# MotorDriver.net
KiCad netlist of a schematic drawn in EAGLE
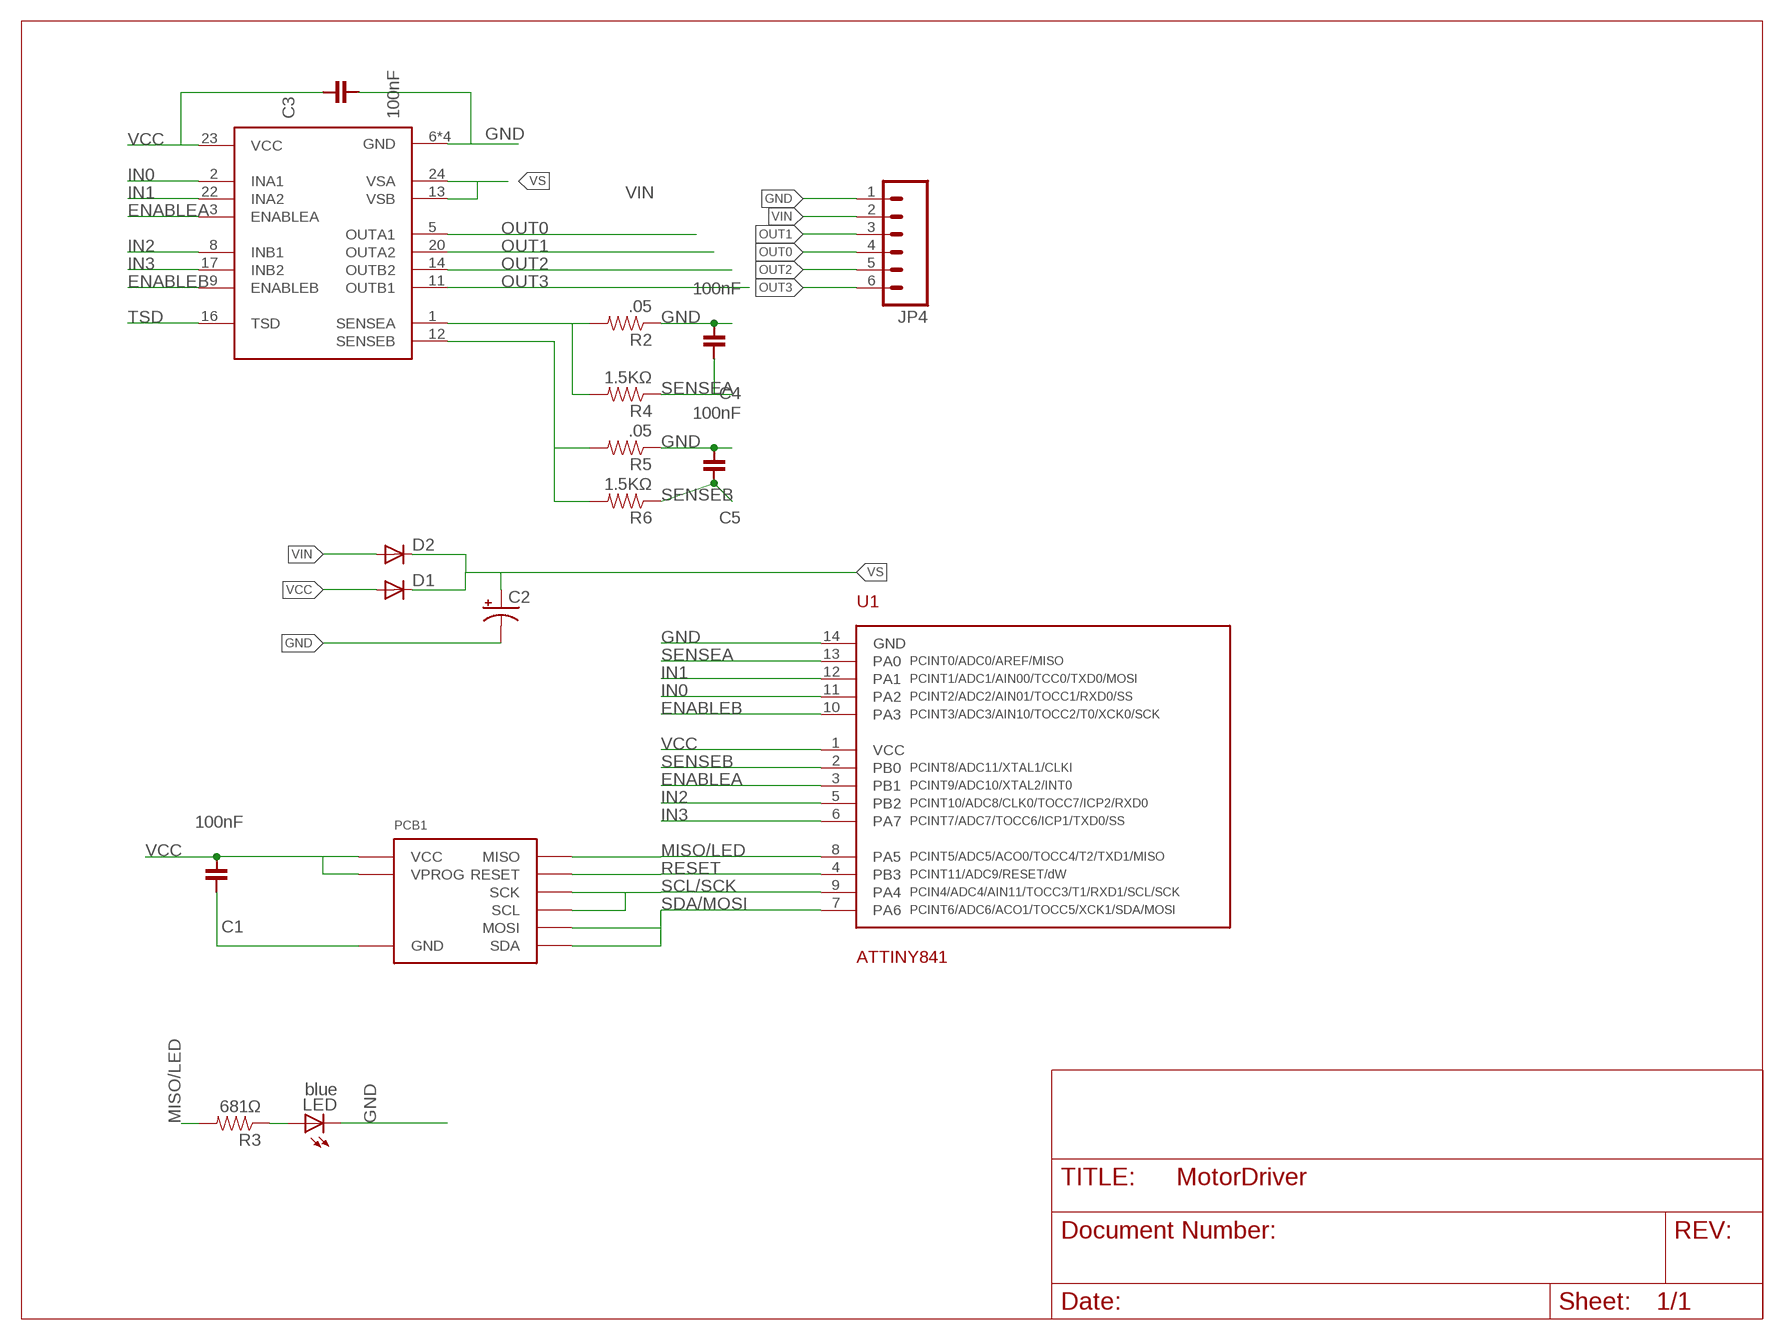
[diagram p0: schematic, sheet 1]

(export (version "E")
  (design (tool "Eeschema 10.0.6"))
  (components
    (comp (ref "C1")
      (value "100nF")
      (footprint "eagle-import:0603")
      (fields (field (name "PARTNUM") "C0603C104K5RACTU"))
      (libsource (lib "eagle-import") (part "CAPACITOR-100NF"))
    )
    (comp (ref "C2")
      (value "CAP_POLC")
      (footprint "eagle-import:PANASONIC_C")
      (fields (field (name "PARTNUM") "EEE-0JA101WR"))
      (libsource (lib "eagle-import") (part "CAP_POLC"))
    )
    (comp (ref "C3")
      (value "100nF")
      (footprint "eagle-import:0603")
      (fields (field (name "PARTNUM") "C0603C104K5RACTU"))
      (libsource (lib "eagle-import") (part "CAPACITOR-100NF"))
    )
    (comp (ref "C4")
      (value "100nF")
      (footprint "eagle-import:0603")
      (fields (field (name "PARTNUM") "C0603C104K5RACTU"))
      (libsource (lib "eagle-import") (part "CAPACITOR-100NF"))
    )
    (comp (ref "C5")
      (value "100nF")
      (footprint "eagle-import:0603")
      (fields (field (name "PARTNUM") "C0603C104K5RACTU"))
      (libsource (lib "eagle-import") (part "CAPACITOR-100NF"))
    )
    (comp (ref "D1")
      (value "DIODESMA")
      (footprint "eagle-import:SMA-DIODE")
      (fields (field (name "PARTNUM") "SSA33L-E3/61T"))
      (libsource (lib "eagle-import") (part "DIODESMA"))
    )
    (comp (ref "D2")
      (value "DIODESMA")
      (footprint "eagle-import:SMA-DIODE")
      (fields (field (name "PARTNUM") "SSA33L-E3/61T"))
      (libsource (lib "eagle-import") (part "DIODESMA"))
    )
    (comp (ref "JP4")
      (value "M063.5MM-6")
      (footprint "eagle-import:SCREWTERMINAL-3.5MM-6")
      (fields (field (name "PARTNUM") "OSTTE060104"))
      (libsource (lib "eagle-import") (part "M063.5MM-6"))
    )
    (comp (ref "LED")
      (value "blue")
      (footprint "eagle-import:0805-LED")
      (fields (field (name "PARTNUM") "LTST-C171TBKT"))
      (libsource (lib "eagle-import") (part "LED-0805-BLUE"))
    )
    (comp (ref "PCB1")
      (value "DEVICE-PCB-TABS")
      (footprint "eagle-import:DEVICE-PCB-TABS")
      (libsource (lib "eagle-import") (part "DEVICE-PCB-TABS"))
    )
    (comp (ref "R2")
      (value ".05")
      (footprint "eagle-import:0805")
      (fields (field (name "PARTNUM") "CSR0805FKR500"))
      (libsource (lib "eagle-import") (part "RESISTOR"))
    )
    (comp (ref "R3")
      (value "681Ω")
      (footprint "eagle-import:0603")
      (fields (field (name "PARTNUM") "ERJ-3EKF6810V"))
      (libsource (lib "eagle-import") (part "RESISTOR-681Ω"))
    )
    (comp (ref "R4")
      (value "1.5KΩ")
      (footprint "eagle-import:0603")
      (fields (field (name "PARTNUM") "ERJ-3EKF1501V"))
      (libsource (lib "eagle-import") (part "RESISTOR-1.5KΩ"))
    )
    (comp (ref "R5")
      (value ".05")
      (footprint "eagle-import:0805")
      (fields (field (name "PARTNUM") "CSR0805FKR500"))
      (libsource (lib "eagle-import") (part "RESISTOR"))
    )
    (comp (ref "R6")
      (value "1.5KΩ")
      (footprint "eagle-import:0603")
      (fields (field (name "PARTNUM") "ERJ-3EKF1501V"))
      (libsource (lib "eagle-import") (part "RESISTOR-1.5KΩ"))
    )
    (comp (ref "U1")
      (value "ATTINY841")
      (footprint "eagle-import:SOIC-14")
      (fields (field (name "PARTNUM") "ATTINY841-SSUR"))
      (libsource (lib "eagle-import") (part "ATTINY841"))
    )
    (comp (ref "U2")
      (value "NJM2670")
      (footprint "eagle-import:SOP-24-E3")
      (fields (field (name "PARTNUM") "NJM2670E3"))
      (libsource (lib "eagle-import") (part "NJM2670"))
    )
  )
  (nets
    (net (code "1") (name "/ENABLEA") (class "Default")
      (node (ref "U1") (pin "3") (pinfunction "PB1_3") (pintype "bidirectional"))
      (node (ref "U2") (pin "3") (pinfunction "ENABLEA_3") (pintype "bidirectional"))
    )
    (net (code "2") (name "/ENABLEB") (class "Default")
      (node (ref "U1") (pin "10") (pinfunction "PA3_10") (pintype "bidirectional"))
      (node (ref "U2") (pin "9") (pinfunction "ENABLEB_9") (pintype "bidirectional"))
    )
    (net (code "3") (name "/IN0") (class "Default")
      (node (ref "U1") (pin "11") (pinfunction "PA2_11") (pintype "bidirectional"))
      (node (ref "U2") (pin "2") (pinfunction "INA1_2") (pintype "bidirectional"))
    )
    (net (code "4") (name "/IN1") (class "Default")
      (node (ref "U1") (pin "12") (pinfunction "PA1_12") (pintype "bidirectional"))
      (node (ref "U2") (pin "22") (pinfunction "INA2_22") (pintype "bidirectional"))
    )
    (net (code "5") (name "/IN2") (class "Default")
      (node (ref "U1") (pin "5") (pinfunction "PB2_5") (pintype "bidirectional"))
      (node (ref "U2") (pin "8") (pinfunction "INB1_8") (pintype "bidirectional"))
    )
    (net (code "6") (name "/IN3") (class "Default")
      (node (ref "U1") (pin "6") (pinfunction "PA7_6") (pintype "bidirectional"))
      (node (ref "U2") (pin "17") (pinfunction "INB2_17") (pintype "bidirectional"))
    )
    (net (code "7") (name "/MISO{slash}LED") (class "Default")
      (node (ref "PCB1") (pin "PROG3") (pinfunction "MISO_PROG3") (pintype "bidirectional"))
      (node (ref "R3") (pin "2") (pinfunction "2_2") (pintype "passive"))
      (node (ref "U1") (pin "8") (pinfunction "PA5_8") (pintype "bidirectional"))
    )
    (net (code "8") (name "/RESET") (class "Default")
      (node (ref "PCB1") (pin "PROG1") (pinfunction "RESET_PROG1") (pintype "bidirectional"))
      (node (ref "U1") (pin "4") (pinfunction "PB3_4") (pintype "bidirectional"))
    )
    (net (code "9") (name "/SCL{slash}SCK") (class "Default")
      (node (ref "PCB1") (pin "BUS3") (pinfunction "SCL_BUS3") (pintype "bidirectional"))
      (node (ref "PCB1") (pin "PROG2") (pinfunction "SCK_PROG2") (pintype "bidirectional"))
      (node (ref "U1") (pin "9") (pinfunction "PA4_9") (pintype "bidirectional"))
    )
    (net (code "10") (name "/SDA{slash}MOSI") (class "Default")
      (node (ref "PCB1") (pin "BUS1") (pinfunction "SDA_BUS1") (pintype "bidirectional"))
      (node (ref "PCB1") (pin "PROG4") (pinfunction "MOSI_PROG4") (pintype "bidirectional"))
      (node (ref "U1") (pin "7") (pinfunction "PA6_7") (pintype "bidirectional"))
    )
    (net (code "11") (name "/SENSEA") (class "Default")
      (node (ref "C4") (pin "1") (pinfunction "1_1") (pintype "passive"))
      (node (ref "R4") (pin "1") (pinfunction "1_1") (pintype "passive"))
      (node (ref "U1") (pin "13") (pinfunction "PA0_13") (pintype "bidirectional"))
    )
    (net (code "12") (name "/SENSEB") (class "Default")
      (node (ref "C5") (pin "1") (pinfunction "1_1") (pintype "passive"))
      (node (ref "R6") (pin "1") (pinfunction "1_1") (pintype "passive"))
      (node (ref "U1") (pin "2") (pinfunction "PB0_2") (pintype "bidirectional"))
    )
    (net (code "13") (name "/TSD") (class "Default")
      (node (ref "U2") (pin "16") (pinfunction "TSD_16") (pintype "bidirectional"))
    )
    (net (code "14") (name "GND") (class "Default")
      (node (ref "C1") (pin "1") (pinfunction "1_1") (pintype "passive"))
      (node (ref "C2") (pin "-") (pinfunction "-_-") (pintype "passive"))
      (node (ref "C3") (pin "2") (pinfunction "2_2") (pintype "passive"))
      (node (ref "C4") (pin "2") (pinfunction "2_2") (pintype "passive"))
      (node (ref "C5") (pin "2") (pinfunction "2_2") (pintype "passive"))
      (node (ref "JP4") (pin "1") (pinfunction "1_1") (pintype "passive"))
      (node (ref "LED") (pin "C") (pinfunction "C_C") (pintype "passive"))
      (node (ref "PCB1") (pin "BUS0") (pinfunction "GND_BUS0") (pintype "bidirectional"))
      (node (ref "R2") (pin "1") (pinfunction "1_1") (pintype "passive"))
      (node (ref "R5") (pin "1") (pinfunction "1_1") (pintype "passive"))
      (node (ref "U1") (pin "14") (pinfunction "GND_14") (pintype "bidirectional"))
      (node (ref "U2") (pin "18") (pinfunction "GND_18") (pintype "bidirectional"))
      (node (ref "U2") (pin "19") (pinfunction "GND_19") (pintype "bidirectional"))
      (node (ref "U2") (pin "6") (pinfunction "GND_6") (pintype "bidirectional"))
      (node (ref "U2") (pin "7") (pinfunction "GND_7") (pintype "bidirectional"))
    )
    (net (code "15") (name "Net-(LED-PadA)") (class "Default")
      (node (ref "LED") (pin "A") (pinfunction "A_A") (pintype "passive"))
      (node (ref "R3") (pin "1") (pinfunction "1_1") (pintype "passive"))
    )
    (net (code "16") (name "Net-(U2-SENSEA)") (class "Default")
      (node (ref "R2") (pin "2") (pinfunction "2_2") (pintype "passive"))
      (node (ref "R4") (pin "2") (pinfunction "2_2") (pintype "passive"))
      (node (ref "U2") (pin "1") (pinfunction "SENSEA_1") (pintype "bidirectional"))
    )
    (net (code "17") (name "Net-(U2-SENSEB)") (class "Default")
      (node (ref "R5") (pin "2") (pinfunction "2_2") (pintype "passive"))
      (node (ref "R6") (pin "2") (pinfunction "2_2") (pintype "passive"))
      (node (ref "U2") (pin "12") (pinfunction "SENSEB_12") (pintype "bidirectional"))
    )
    (net (code "18") (name "OUT0") (class "Default")
      (node (ref "JP4") (pin "4") (pinfunction "4_4") (pintype "passive"))
      (node (ref "U2") (pin "5") (pinfunction "OUTA1_5") (pintype "bidirectional"))
    )
    (net (code "19") (name "OUT1") (class "Default")
      (node (ref "JP4") (pin "3") (pinfunction "3_3") (pintype "passive"))
      (node (ref "U2") (pin "20") (pinfunction "OUTA2_20") (pintype "bidirectional"))
    )
    (net (code "20") (name "OUT2") (class "Default")
      (node (ref "JP4") (pin "5") (pinfunction "5_5") (pintype "passive"))
      (node (ref "U2") (pin "14") (pinfunction "OUTB2_14") (pintype "bidirectional"))
    )
    (net (code "21") (name "OUT3") (class "Default")
      (node (ref "JP4") (pin "6") (pinfunction "6_6") (pintype "passive"))
      (node (ref "U2") (pin "11") (pinfunction "OUTB1_11") (pintype "bidirectional"))
    )
    (net (code "22") (name "VCC") (class "Default")
      (node (ref "C1") (pin "2") (pinfunction "2_2") (pintype "passive"))
      (node (ref "C3") (pin "1") (pinfunction "1_1") (pintype "passive"))
      (node (ref "D1") (pin "A") (pinfunction "A_A") (pintype "passive"))
      (node (ref "PCB1") (pin "BUS2") (pinfunction "VCC_BUS2") (pintype "bidirectional"))
      (node (ref "PCB1") (pin "PROG0") (pinfunction "VPROG_PROG0") (pintype "bidirectional"))
      (node (ref "U1") (pin "1") (pinfunction "VCC_1") (pintype "bidirectional"))
      (node (ref "U2") (pin "23") (pinfunction "VCC_23") (pintype "bidirectional"))
    )
    (net (code "23") (name "VIN") (class "Default")
      (node (ref "D2") (pin "A") (pinfunction "A_A") (pintype "passive"))
      (node (ref "JP4") (pin "2") (pinfunction "2_2") (pintype "passive"))
    )
    (net (code "24") (name "VS") (class "Default")
      (node (ref "C2") (pin "+") (pinfunction "+_+") (pintype "passive"))
      (node (ref "D1") (pin "C") (pinfunction "C_C") (pintype "passive"))
      (node (ref "D2") (pin "C") (pinfunction "C_C") (pintype "passive"))
      (node (ref "U2") (pin "13") (pinfunction "VSB_13") (pintype "bidirectional"))
      (node (ref "U2") (pin "24") (pinfunction "VSA_24") (pintype "bidirectional"))
    )
  )
)
